# FRAM.net
KiCad netlist of a schematic drawn in Altium Designer
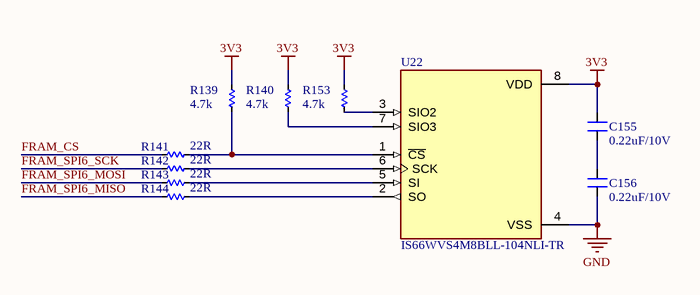
[diagram p0: FRAM.SchDoc]

(export (version "E")
  (design (tool "Eeschema 10.0.6"))
  (components
    (comp (ref "C155")
      (value "0.22uF/10V")
      (footprint "CAP_C_1608X80")
      (libsource (lib "EXP_HW_V3") (part "Capacitors"))
    )
    (comp (ref "C156")
      (value "0.22uF/10V")
      (footprint "CAP_C_1608X80")
      (libsource (lib "EXP_HW_V3") (part "Capacitors"))
    )
    (comp (ref "R139")
      (value "4.7k")
      (footprint "RES_C_1608X60")
      (description "SMD")
      (fields
        (field (name "MANUFACTURER") "Generic Components")
        (field (name "PUBLISHER") "Altium Hobart Technology Centre")
      )
      (libsource (lib "EXP_HW_V3") (part "Res SMD"))
    )
    (comp (ref "R140")
      (value "4.7k")
      (footprint "RES_C_1608X60")
      (description "SMD")
      (fields
        (field (name "MANUFACTURER") "Generic Components")
        (field (name "PUBLISHER") "Altium Hobart Technology Centre")
      )
      (libsource (lib "EXP_HW_V3") (part "Res SMD"))
    )
    (comp (ref "R141")
      (value "22R")
      (footprint "RES_C_1608X60")
      (description "SMD")
      (fields
        (field (name "MANUFACTURER") "Generic Components")
        (field (name "PUBLISHER") "Altium Hobart Technology Centre")
      )
      (libsource (lib "EXP_HW_V3") (part "Res SMD"))
    )
    (comp (ref "R142")
      (value "22R")
      (footprint "RES_C_1608X60")
      (description "SMD")
      (fields
        (field (name "MANUFACTURER") "Generic Components")
        (field (name "PUBLISHER") "Altium Hobart Technology Centre")
      )
      (libsource (lib "EXP_HW_V3") (part "Res SMD"))
    )
    (comp (ref "R143")
      (value "22R")
      (footprint "RES_C_1608X60")
      (description "SMD")
      (fields
        (field (name "MANUFACTURER") "Generic Components")
        (field (name "PUBLISHER") "Altium Hobart Technology Centre")
      )
      (libsource (lib "EXP_HW_V3") (part "Res SMD"))
    )
    (comp (ref "R144")
      (value "22R")
      (footprint "RES_C_1608X60")
      (description "SMD")
      (fields
        (field (name "MANUFACTURER") "Generic Components")
        (field (name "PUBLISHER") "Altium Hobart Technology Centre")
      )
      (libsource (lib "EXP_HW_V3") (part "Res SMD"))
    )
    (comp (ref "R153")
      (value "4.7k")
      (footprint "RES_C_1608X60")
      (description "SMD")
      (fields
        (field (name "MANUFACTURER") "Generic Components")
        (field (name "PUBLISHER") "Altium Hobart Technology Centre")
      )
      (libsource (lib "EXP_HW_V3") (part "Res SMD"))
    )
    (comp (ref "U22")
      (value "IS66WVS4M8BLL-104NLI-TR")
      (footprint "IS66WVS4M8BLL-104NLI-TR")
      (description "IC PSRAM 32MBIT SPI QPI 8SOIC")
      (fields (field (name "MF") "Fujitsu Electronics") (field (name "DIGI-KEY_PART_NUMBER") "865-1286-1-ND"))
      (libsource (lib "EXP_HW_V3") (part "IS66WVS4M8BLL-104NLI-TR"))
    )
  )
  (nets
    (net (code "1") (name "/FRAM_CS") (class "Default")
      (node (ref "R141") (pin "1") (pinfunction "1_1") (pintype "passive"))
    )
    (net (code "2") (name "/FRAM_SPI6_MISO") (class "Default")
      (node (ref "R144") (pin "1") (pinfunction "1_1") (pintype "passive"))
    )
    (net (code "3") (name "/FRAM_SPI6_MOSI") (class "Default")
      (node (ref "R143") (pin "1") (pinfunction "1_1") (pintype "passive"))
    )
    (net (code "4") (name "/FRAM_SPI6_SCK") (class "Default")
      (node (ref "R142") (pin "1") (pinfunction "1_1") (pintype "passive"))
    )
    (net (code "5") (name "3V3") (class "Default")
      (node (ref "C155") (pin "2") (pinfunction "2_2") (pintype "passive"))
      (node (ref "R139") (pin "1") (pinfunction "1_1") (pintype "passive"))
      (node (ref "R140") (pin "1") (pinfunction "1_1") (pintype "passive"))
      (node (ref "R153") (pin "1") (pinfunction "1_1") (pintype "passive"))
      (node (ref "U22") (pin "8") (pinfunction "VDD_8") (pintype "power_in"))
    )
    (net (code "6") (name "GND") (class "Default")
      (node (ref "C156") (pin "1") (pinfunction "1_1") (pintype "passive"))
      (node (ref "U22") (pin "4") (pinfunction "VSS_4") (pintype "power_in"))
    )
    (net (code "7") (name "Net-(C155-Pad1)") (class "Default")
      (node (ref "C155") (pin "1") (pinfunction "1_1") (pintype "passive"))
      (node (ref "C156") (pin "2") (pinfunction "2_2") (pintype "passive"))
    )
    (net (code "8") (name "Net-(U22-SCK)") (class "Default")
      (node (ref "R142") (pin "2") (pinfunction "2_2") (pintype "passive"))
      (node (ref "U22") (pin "6") (pinfunction "SCK_6") (pintype "input"))
    )
    (net (code "9") (name "Net-(U22-SI)") (class "Default")
      (node (ref "R143") (pin "2") (pinfunction "2_2") (pintype "passive"))
      (node (ref "U22") (pin "5") (pinfunction "SI_5") (pintype "input"))
    )
    (net (code "10") (name "Net-(U22-SIO2)") (class "Default")
      (node (ref "R153") (pin "2") (pinfunction "2_2") (pintype "passive"))
      (node (ref "U22") (pin "3") (pinfunction "SIO2_3") (pintype "input"))
    )
    (net (code "11") (name "Net-(U22-SIO3)") (class "Default")
      (node (ref "R140") (pin "2") (pinfunction "2_2") (pintype "passive"))
      (node (ref "U22") (pin "7") (pinfunction "SIO3_7") (pintype "input"))
    )
    (net (code "12") (name "Net-(U22-SO)") (class "Default")
      (node (ref "R144") (pin "2") (pinfunction "2_2") (pintype "passive"))
      (node (ref "U22") (pin "2") (pinfunction "SO_2") (pintype "output"))
    )
    (net (code "13") (name "Net-(U22-~{CS})") (class "Default")
      (node (ref "R139") (pin "2") (pinfunction "2_2") (pintype "passive"))
      (node (ref "R141") (pin "2") (pinfunction "2_2") (pintype "passive"))
      (node (ref "U22") (pin "1") (pinfunction "~{CS}_1") (pintype "input"))
    )
  )
)
